# Power.net
KiCad netlist of a schematic drawn in Altium Designer
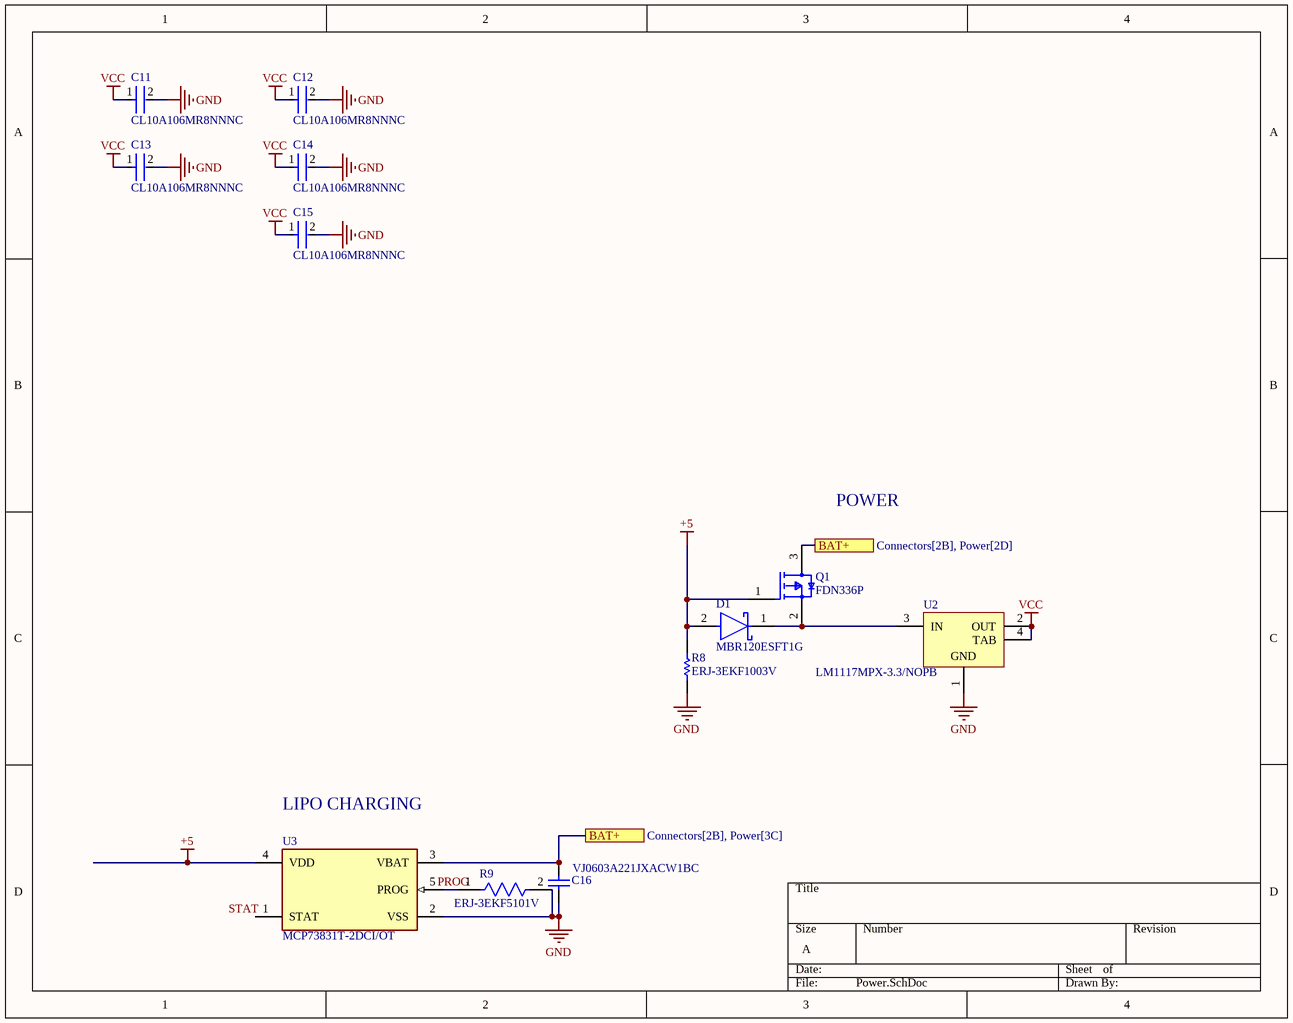
[diagram p0: Power.SchDoc]

(export (version "E")
  (design (tool "Eeschema 10.0.6"))
  (components
    (comp (ref "C11")
      (value "CL10A106MR8NNNC")
      (footprint "FP-CL10-IPC_C")
      (description "Cap Ceramic 10uF 4V X5R ±20% Pad SMD 0603 +85°C T/R")
      (fields (field (name "TOLERANCE") "20%"))
      (libsource (lib "Altium Content Vault") (part "b4654b650e69147ec39a6b967a45e02"))
    )
    (comp (ref "C12")
      (value "CL10A106MR8NNNC")
      (footprint "FP-CL10-IPC_C")
      (description "Cap Ceramic 10uF 4V X5R ±20% Pad SMD 0603 +85°C T/R")
      (fields (field (name "TOLERANCE") "20%"))
      (libsource (lib "Altium Content Vault") (part "b4654b650e69147ec39a6b967a45e02"))
    )
    (comp (ref "C13")
      (value "CL10A106MR8NNNC")
      (footprint "FP-CL10-IPC_C")
      (description "Cap Ceramic 10uF 4V X5R ±20% Pad SMD 0603 +85°C T/R")
      (fields (field (name "TOLERANCE") "20%"))
      (libsource (lib "Altium Content Vault") (part "b4654b650e69147ec39a6b967a45e02"))
    )
    (comp (ref "C14")
      (value "CL10A106MR8NNNC")
      (footprint "FP-CL10-IPC_C")
      (description "Cap Ceramic 10uF 4V X5R ±20% Pad SMD 0603 +85°C T/R")
      (fields (field (name "TOLERANCE") "20%"))
      (libsource (lib "Altium Content Vault") (part "b4654b650e69147ec39a6b967a45e02"))
    )
    (comp (ref "C15")
      (value "CL10A106MR8NNNC")
      (footprint "FP-CL10-IPC_C")
      (description "Cap Ceramic 10uF 4V X5R ±20% Pad SMD 0603 +85°C T/R")
      (fields (field (name "TOLERANCE") "20%"))
      (libsource (lib "Altium Content Vault") (part "b4654b650e69147ec39a6b967a45e02"))
    )
    (comp (ref "C16")
      (value "VJ0603A221JXACW1BC")
      (footprint "CAPC1608X95X40ML15T15")
      (fields (field (name "MANUFACTURER") "Vitramon"))
      (libsource (lib "Altium Content Vault") (part "CAP"))
    )
    (comp (ref "D1")
      (value "MBR120ESFT1G")
      (footprint "On_Semiconductor_498_MFG")
      (libsource (lib "Altium Content Vault") (part "MBR120ESFT1G"))
    )
    (comp (ref "Q1")
      (value "FDN336P")
      (footprint "FP-527AG-IPC_A")
      (description "MOSFET P-CH 20V 1.3A SSOT3")
      (libsource (lib "Altium Content Vault") (part "274ba75a4227b453460520a6808ef61"))
    )
    (comp (ref "R8")
      (value "ERJ-3EKF1003V")
      (footprint "RESC1608X55X30ML15T15")
      (fields (field (name "MANUFACTURER") "Panasonic"))
      (libsource (lib "Altium Content Vault") (part "RES"))
    )
    (comp (ref "R9")
      (value "ERJ-3EKF5101V")
      (footprint "FP-ERJ3EK-MFG")
      (description "RES SMD 5.1K OHM 1% 1/10W 0603")
      (fields (field (name "TOLERANCE") "1%"))
      (libsource (lib "Altium Content Vault") (part "1029c3af85768c4190bb7ad29bc67b5"))
    )
    (comp (ref "U2")
      (value "LM1117MPX-3.3/NOPB")
      (footprint "DCY0004A_L")
      (description "800mA Low-Dropout Linear Regulator, 4-pin SOT-223, Pb-Free")
      (fields (field (name "MANUFACTURER") "Texas Instruments"))
      (libsource (lib "Altium Content Vault") (part "PM-REG-LM1086-SOT4"))
    )
    (comp (ref "U3")
      (value "MCP73831T-2DCI/OT")
      (footprint "FP-C04-091-OT-IPC_B")
      (description "IC CONTROLLR LI-ION 4.2V SOT23-5")
      (libsource (lib "Altium Content Vault") (part "61f5a3bb3429d9e0caadea342aa3b19"))
    )
  )
  (nets
    (net (code "1") (name "+5") (class "Default")
      (node (ref "D1") (pin "2") (pinfunction "A_2") (pintype "passive"))
      (node (ref "Q1") (pin "1") (pinfunction "G_1") (pintype "passive"))
      (node (ref "R8") (pin "2") (pinfunction "2_2") (pintype "passive"))
      (node (ref "U3") (pin "4") (pinfunction "VDD_4") (pintype "open_emitter"))
    )
    (net (code "2") (name "/BAT+") (class "Default")
      (node (ref "C16") (pin "2") (pinfunction "2_2") (pintype "passive"))
      (node (ref "Q1") (pin "3") (pinfunction "D_3") (pintype "passive"))
      (node (ref "U3") (pin "3") (pinfunction "VBAT_3") (pintype "power_in"))
    )
    (net (code "5") (name "GND") (class "Default")
      (node (ref "C11") (pin "2") (pinfunction "2_2") (pintype "passive"))
      (node (ref "C12") (pin "2") (pinfunction "2_2") (pintype "passive"))
      (node (ref "C13") (pin "2") (pinfunction "2_2") (pintype "passive"))
      (node (ref "C14") (pin "2") (pinfunction "2_2") (pintype "passive"))
      (node (ref "C15") (pin "2") (pinfunction "2_2") (pintype "passive"))
      (node (ref "C16") (pin "1") (pinfunction "1_1") (pintype "passive"))
      (node (ref "R8") (pin "1") (pinfunction "1_1") (pintype "passive"))
      (node (ref "R9") (pin "2") (pinfunction "2_2") (pintype "passive"))
      (node (ref "U2") (pin "1") (pinfunction "GND_1") (pintype "power_in"))
      (node (ref "U3") (pin "2") (pinfunction "VSS_2") (pintype "power_in"))
    )
    (net (code "6") (name "Net-(D1-C)") (class "Default")
      (node (ref "D1") (pin "1") (pinfunction "C_1") (pintype "passive"))
      (node (ref "Q1") (pin "2") (pinfunction "S_2") (pintype "passive"))
      (node (ref "U2") (pin "3") (pinfunction "IN_3") (pintype "power_in"))
    )
    (net (code "7") (name "Net-(U3-PROG)") (class "Default")
      (node (ref "R9") (pin "1") (pinfunction "1_1") (pintype "passive"))
      (node (ref "U3") (pin "5") (pinfunction "PROG_5") (pintype "input"))
    )
    (net (code "8") (name "VCC") (class "Default")
      (node (ref "C11") (pin "1") (pinfunction "1_1") (pintype "passive"))
      (node (ref "C12") (pin "1") (pinfunction "1_1") (pintype "passive"))
      (node (ref "C13") (pin "1") (pinfunction "1_1") (pintype "passive"))
      (node (ref "C14") (pin "1") (pinfunction "1_1") (pintype "passive"))
      (node (ref "C15") (pin "1") (pinfunction "1_1") (pintype "passive"))
      (node (ref "U2") (pin "2") (pinfunction "OUT_2") (pintype "power_in"))
      (node (ref "U2") (pin "4") (pinfunction "TAB_4") (pintype "power_in"))
    )
    (net (code "9") (name "unconnected-(U3-STAT-Pad1)") (class "Default")
      (node (ref "U3") (pin "1") (pinfunction "STAT_1") (pintype "passive"))
    )
  )
)
